# nguyen_ly.net
KiCad netlist of a schematic drawn in Altium Designer
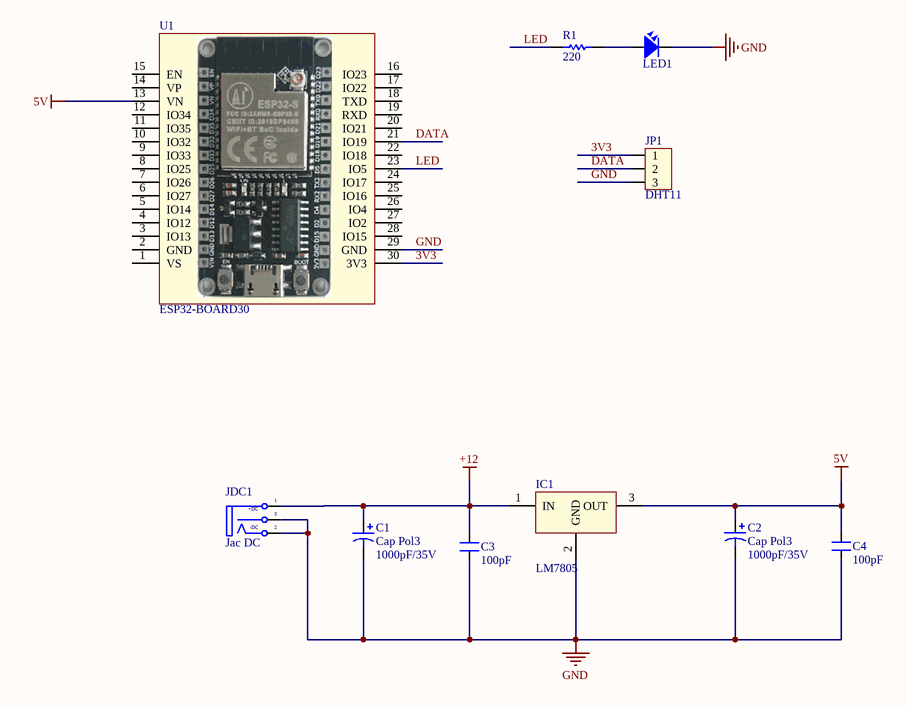
[diagram p0: nguyen_ly.SchDoc]

(export (version "E")
  (design (tool "Eeschema 10.0.6"))
  (components
    (comp (ref "C1")
      (value "Cap Pol3")
      (footprint "CP2/5")
      (description "Polarized Capacitor (Surface Mount)")
      (fields (field (name "ALTIUM_VALUE") "1000pF/35V") (field (name "PUBLISHER") "Altium Limited"))
      (libsource (lib "Thuvien3D") (part "Cap Pol3"))
    )
    (comp (ref "C2")
      (value "Cap Pol3")
      (footprint "CP2/5")
      (description "Polarized Capacitor (Surface Mount)")
      (fields (field (name "ALTIUM_VALUE") "1000pF/35V") (field (name "PUBLISHER") "Altium Limited"))
      (libsource (lib "Thuvien3D") (part "Cap Pol3"))
    )
    (comp (ref "C3")
      (value "100pF")
      (footprint "CN1")
      (description "Cap np  1pF - 472pF")
      (libsource (lib "Thuvien3D") (part "CN1"))
    )
    (comp (ref "C4")
      (value "100pF")
      (footprint "CN1")
      (description "Cap np  1pF - 472pF")
      (libsource (lib "Thuvien3D") (part "CN1"))
    )
    (comp (ref "IC1")
      (value "LM7805")
      (footprint "QTO-220")
      (description "On ap +, from + 5 to + 24VDC")
      (libsource (lib "Thuvien3D") (part "LM78xx"))
    )
    (comp (ref "JDC1")
      (value "Jac DC")
      (footprint "DC-IN")
      (description "Jac DC input")
      (libsource (lib "PART_VDE") (part "DCIN"))
    )
    (comp (ref "JP1")
      (value "DHT11")
      (footprint "CON3")
      (description "Connector 3")
      (libsource (lib "Thuvien3D") (part "Con3"))
    )
    (comp (ref "LED1")
      (value "LED")
      (footprint "LED-3")
      (description "LED Single colour Green and Red")
      (libsource (lib "Thuvien3D") (part "LED"))
    )
    (comp (ref "R1")
      (value "220")
      (footprint "R1/4W")
      (description "Resistor")
      (fields
        (field (name "MANUFACTURER") "Generic Components")
        (field (name "Comment") "Res1")
        (field (name "PUBLISHER") "Altium Hobart Technology Centre")
      )
      (libsource (lib "Thuvien3D") (part "Res1_1"))
    )
    (comp (ref "U1")
      (value "ESP32-BOARD30")
      (footprint "ESP32-BOARD30-900")
      (libsource (lib "PART_VDE") (part "ESP32-BOARD30"))
    )
  )
  (nets
    (net (code "1") (name "+12") (class "Default")
      (node (ref "C1") (pin "1") (pinfunction "1_1") (pintype "passive"))
      (node (ref "C3") (pin "2") (pinfunction "2_2") (pintype "passive"))
      (node (ref "IC1") (pin "1") (pinfunction "IN_1") (pintype "passive"))
      (node (ref "JDC1") (pin "1") (pinfunction "+DC_1") (pintype "passive"))
    )
    (net (code "2") (name "/3V3") (class "Default")
      (node (ref "JP1") (pin "1") (pinfunction "1_1") (pintype "passive"))
      (node (ref "U1") (pin "30") (pinfunction "3V3_30") (pintype "passive"))
    )
    (net (code "3") (name "/DATA") (class "Default")
      (node (ref "JP1") (pin "2") (pinfunction "2_2") (pintype "passive"))
      (node (ref "U1") (pin "21") (pinfunction "IO19_21") (pintype "passive"))
    )
    (net (code "4") (name "/LED") (class "Default")
      (node (ref "R1") (pin "2") (pinfunction "2_2") (pintype "passive"))
      (node (ref "U1") (pin "23") (pinfunction "IO5_23") (pintype "passive"))
    )
    (net (code "5") (name "5V") (class "Default")
      (node (ref "C2") (pin "1") (pinfunction "1_1") (pintype "passive"))
      (node (ref "C4") (pin "2") (pinfunction "2_2") (pintype "passive"))
      (node (ref "IC1") (pin "3") (pinfunction "OUT_3") (pintype "passive"))
      (node (ref "U1") (pin "13") (pinfunction "VN_13") (pintype "passive"))
    )
    (net (code "6") (name "GND") (class "Default")
      (node (ref "C1") (pin "2") (pinfunction "2_2") (pintype "passive"))
      (node (ref "C2") (pin "2") (pinfunction "2_2") (pintype "passive"))
      (node (ref "C3") (pin "1") (pinfunction "1_1") (pintype "passive"))
      (node (ref "C4") (pin "1") (pinfunction "1_1") (pintype "passive"))
      (node (ref "IC1") (pin "2") (pinfunction "GND_2") (pintype "passive"))
      (node (ref "JDC1") (pin "2") (pinfunction "TN_2") (pintype "passive"))
      (node (ref "JDC1") (pin "3") (pinfunction "S_3") (pintype "power_in"))
      (node (ref "JP1") (pin "3") (pinfunction "3_3") (pintype "passive"))
      (node (ref "LED1") (pin "2") (pinfunction "2_2") (pintype "passive"))
      (node (ref "U1") (pin "29") (pinfunction "GND_29") (pintype "passive"))
    )
    (net (code "7") (name "Net-(LED1-Pad1)") (class "Default")
      (node (ref "LED1") (pin "1") (pinfunction "1_1") (pintype "passive"))
      (node (ref "R1") (pin "1") (pinfunction "1_1") (pintype "passive"))
    )
    (net (code "8") (name "unconnected-(U1-EN-Pad15)") (class "Default")
      (node (ref "U1") (pin "15") (pinfunction "EN_15") (pintype "passive"))
    )
    (net (code "9") (name "unconnected-(U1-GND-Pad2)") (class "Default")
      (node (ref "U1") (pin "2") (pinfunction "GND_2") (pintype "passive"))
    )
    (net (code "10") (name "unconnected-(U1-IO2-Pad27)") (class "Default")
      (node (ref "U1") (pin "27") (pinfunction "IO2_27") (pintype "passive"))
    )
    (net (code "11") (name "unconnected-(U1-IO4-Pad26)") (class "Default")
      (node (ref "U1") (pin "26") (pinfunction "IO4_26") (pintype "passive"))
    )
    (net (code "12") (name "unconnected-(U1-IO12-Pad4)") (class "Default")
      (node (ref "U1") (pin "4") (pinfunction "IO12_4") (pintype "passive"))
    )
    (net (code "13") (name "unconnected-(U1-IO13-Pad3)") (class "Default")
      (node (ref "U1") (pin "3") (pinfunction "IO13_3") (pintype "passive"))
    )
    (net (code "14") (name "unconnected-(U1-IO14-Pad5)") (class "Default")
      (node (ref "U1") (pin "5") (pinfunction "IO14_5") (pintype "passive"))
    )
    (net (code "15") (name "unconnected-(U1-IO15-Pad28)") (class "Default")
      (node (ref "U1") (pin "28") (pinfunction "IO15_28") (pintype "passive"))
    )
    (net (code "16") (name "unconnected-(U1-IO16-Pad25)") (class "Default")
      (node (ref "U1") (pin "25") (pinfunction "IO16_25") (pintype "passive"))
    )
    (net (code "17") (name "unconnected-(U1-IO17-Pad24)") (class "Default")
      (node (ref "U1") (pin "24") (pinfunction "IO17_24") (pintype "passive"))
    )
    (net (code "18") (name "unconnected-(U1-IO18-Pad22)") (class "Default")
      (node (ref "U1") (pin "22") (pinfunction "IO18_22") (pintype "passive"))
    )
    (net (code "19") (name "unconnected-(U1-IO21-Pad20)") (class "Default")
      (node (ref "U1") (pin "20") (pinfunction "IO21_20") (pintype "passive"))
    )
    (net (code "20") (name "unconnected-(U1-IO22-Pad17)") (class "Default")
      (node (ref "U1") (pin "17") (pinfunction "IO22_17") (pintype "passive"))
    )
    (net (code "21") (name "unconnected-(U1-IO23-Pad16)") (class "Default")
      (node (ref "U1") (pin "16") (pinfunction "IO23_16") (pintype "passive"))
    )
    (net (code "22") (name "unconnected-(U1-IO25-Pad8)") (class "Default")
      (node (ref "U1") (pin "8") (pinfunction "IO25_8") (pintype "passive"))
    )
    (net (code "23") (name "unconnected-(U1-IO26-Pad7)") (class "Default")
      (node (ref "U1") (pin "7") (pinfunction "IO26_7") (pintype "passive"))
    )
    (net (code "24") (name "unconnected-(U1-IO27-Pad6)") (class "Default")
      (node (ref "U1") (pin "6") (pinfunction "IO27_6") (pintype "passive"))
    )
    (net (code "25") (name "unconnected-(U1-IO32-Pad10)") (class "Default")
      (node (ref "U1") (pin "10") (pinfunction "IO32_10") (pintype "passive"))
    )
    (net (code "26") (name "unconnected-(U1-IO33-Pad9)") (class "Default")
      (node (ref "U1") (pin "9") (pinfunction "IO33_9") (pintype "passive"))
    )
    (net (code "27") (name "unconnected-(U1-IO34-Pad12)") (class "Default")
      (node (ref "U1") (pin "12") (pinfunction "IO34_12") (pintype "passive"))
    )
    (net (code "28") (name "unconnected-(U1-IO35-Pad11)") (class "Default")
      (node (ref "U1") (pin "11") (pinfunction "IO35_11") (pintype "passive"))
    )
    (net (code "29") (name "unconnected-(U1-RXD-Pad19)") (class "Default")
      (node (ref "U1") (pin "19") (pinfunction "RXD_19") (pintype "passive"))
    )
    (net (code "30") (name "unconnected-(U1-TXD-Pad18)") (class "Default")
      (node (ref "U1") (pin "18") (pinfunction "TXD_18") (pintype "passive"))
    )
    (net (code "31") (name "unconnected-(U1-VP-Pad14)") (class "Default")
      (node (ref "U1") (pin "14") (pinfunction "VP_14") (pintype "passive"))
    )
    (net (code "32") (name "unconnected-(U1-VS-Pad1)") (class "Default")
      (node (ref "U1") (pin "1") (pinfunction "VS_1") (pintype "passive"))
    )
  )
)
